# Interface_-_EEPROM.net
KiCad netlist of a schematic drawn in Altium Designer
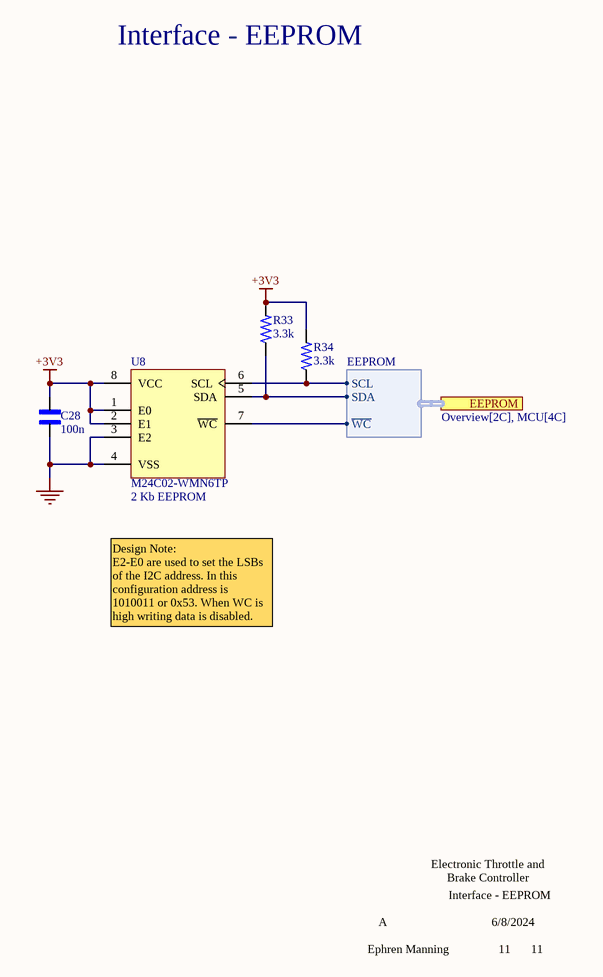
[diagram p0: Interface - EEPROM.SchDoc]

(export (version "E")
  (design (tool "Eeschema 10.0.6"))
  (components
    (comp (ref "C28")
      (value "100n")
      (footprint "CAP_0402-Footprint-1")
      (description "100nF 10V 10% 0402 CAP")
      (fields (field (name "DIGIKEY PART NUMBER") "1276-1002-1-ND"))
      (libsource (lib "SAE @ UIC Formula Electric") (part "CAP_0402-Symbol-1"))
    )
    (comp (ref "R33")
      (value "3.3k")
      (footprint "RES_0402-Footprint-1")
      (description "3.3k 1% 1/16W 0402 Thick Film")
      (fields (field (name "DIGIKEY PART NUMBER") "311-3.30KLRCT-ND"))
      (libsource (lib "SAE @ UIC Formula Electric") (part "RES_0402_Symbol"))
    )
    (comp (ref "R34")
      (value "3.3k")
      (footprint "RES_0402-Footprint-1")
      (description "3.3k 1% 1/16W 0402 Thick Film")
      (fields (field (name "DIGIKEY PART NUMBER") "311-3.30KLRCT-ND"))
      (libsource (lib "SAE @ UIC Formula Electric") (part "RES_0402_Symbol"))
    )
    (comp (ref "U8")
      (value "M24C02-WMN6TP")
      (footprint "FP-SO8N-SO-A-IPC_B")
      (description "2Kb I2C EEPROM")
      (fields (field (name "DIGIKEY PART NUMBER") "497-8552-1-ND"))
      (libsource (lib "SAE @ UIC Formula Electric") (part "M24C02-WMN6TP-Symbol"))
    )
  )
  (nets
    (net (code "2") (name "+3V3") (class "Default")
      (node (ref "C28") (pin "2") (pinfunction "2_2") (pintype "passive"))
      (node (ref "R33") (pin "2") (pinfunction "2_2") (pintype "passive"))
      (node (ref "R34") (pin "2") (pinfunction "2_2") (pintype "passive"))
      (node (ref "U8") (pin "1") (pinfunction "E0_1") (pintype "passive"))
      (node (ref "U8") (pin "2") (pinfunction "E1_2") (pintype "passive"))
      (node (ref "U8") (pin "8") (pinfunction "VCC_8") (pintype "power_in"))
    )
    (net (code "3") (name "/SCL") (class "Default")
      (node (ref "R34") (pin "1") (pinfunction "1_1") (pintype "passive"))
      (node (ref "U8") (pin "6") (pinfunction "SCL_6") (pintype "passive"))
    )
    (net (code "4") (name "/SDA") (class "Default")
      (node (ref "R33") (pin "1") (pinfunction "1_1") (pintype "passive"))
      (node (ref "U8") (pin "5") (pinfunction "SDA_5") (pintype "passive"))
    )
    (net (code "6") (name "/~{WC}") (class "Default")
      (node (ref "U8") (pin "7") (pinfunction "~{WC}_7") (pintype "passive"))
    )
    (net (code "7") (name "GND") (class "Default")
      (node (ref "C28") (pin "1") (pinfunction "1_1") (pintype "passive"))
      (node (ref "U8") (pin "3") (pinfunction "E2_3") (pintype "passive"))
      (node (ref "U8") (pin "4") (pinfunction "VSS_4") (pintype "power_in"))
    )
  )
)
